# 11-LED.net
KiCad netlist of a schematic drawn in Altium Designer
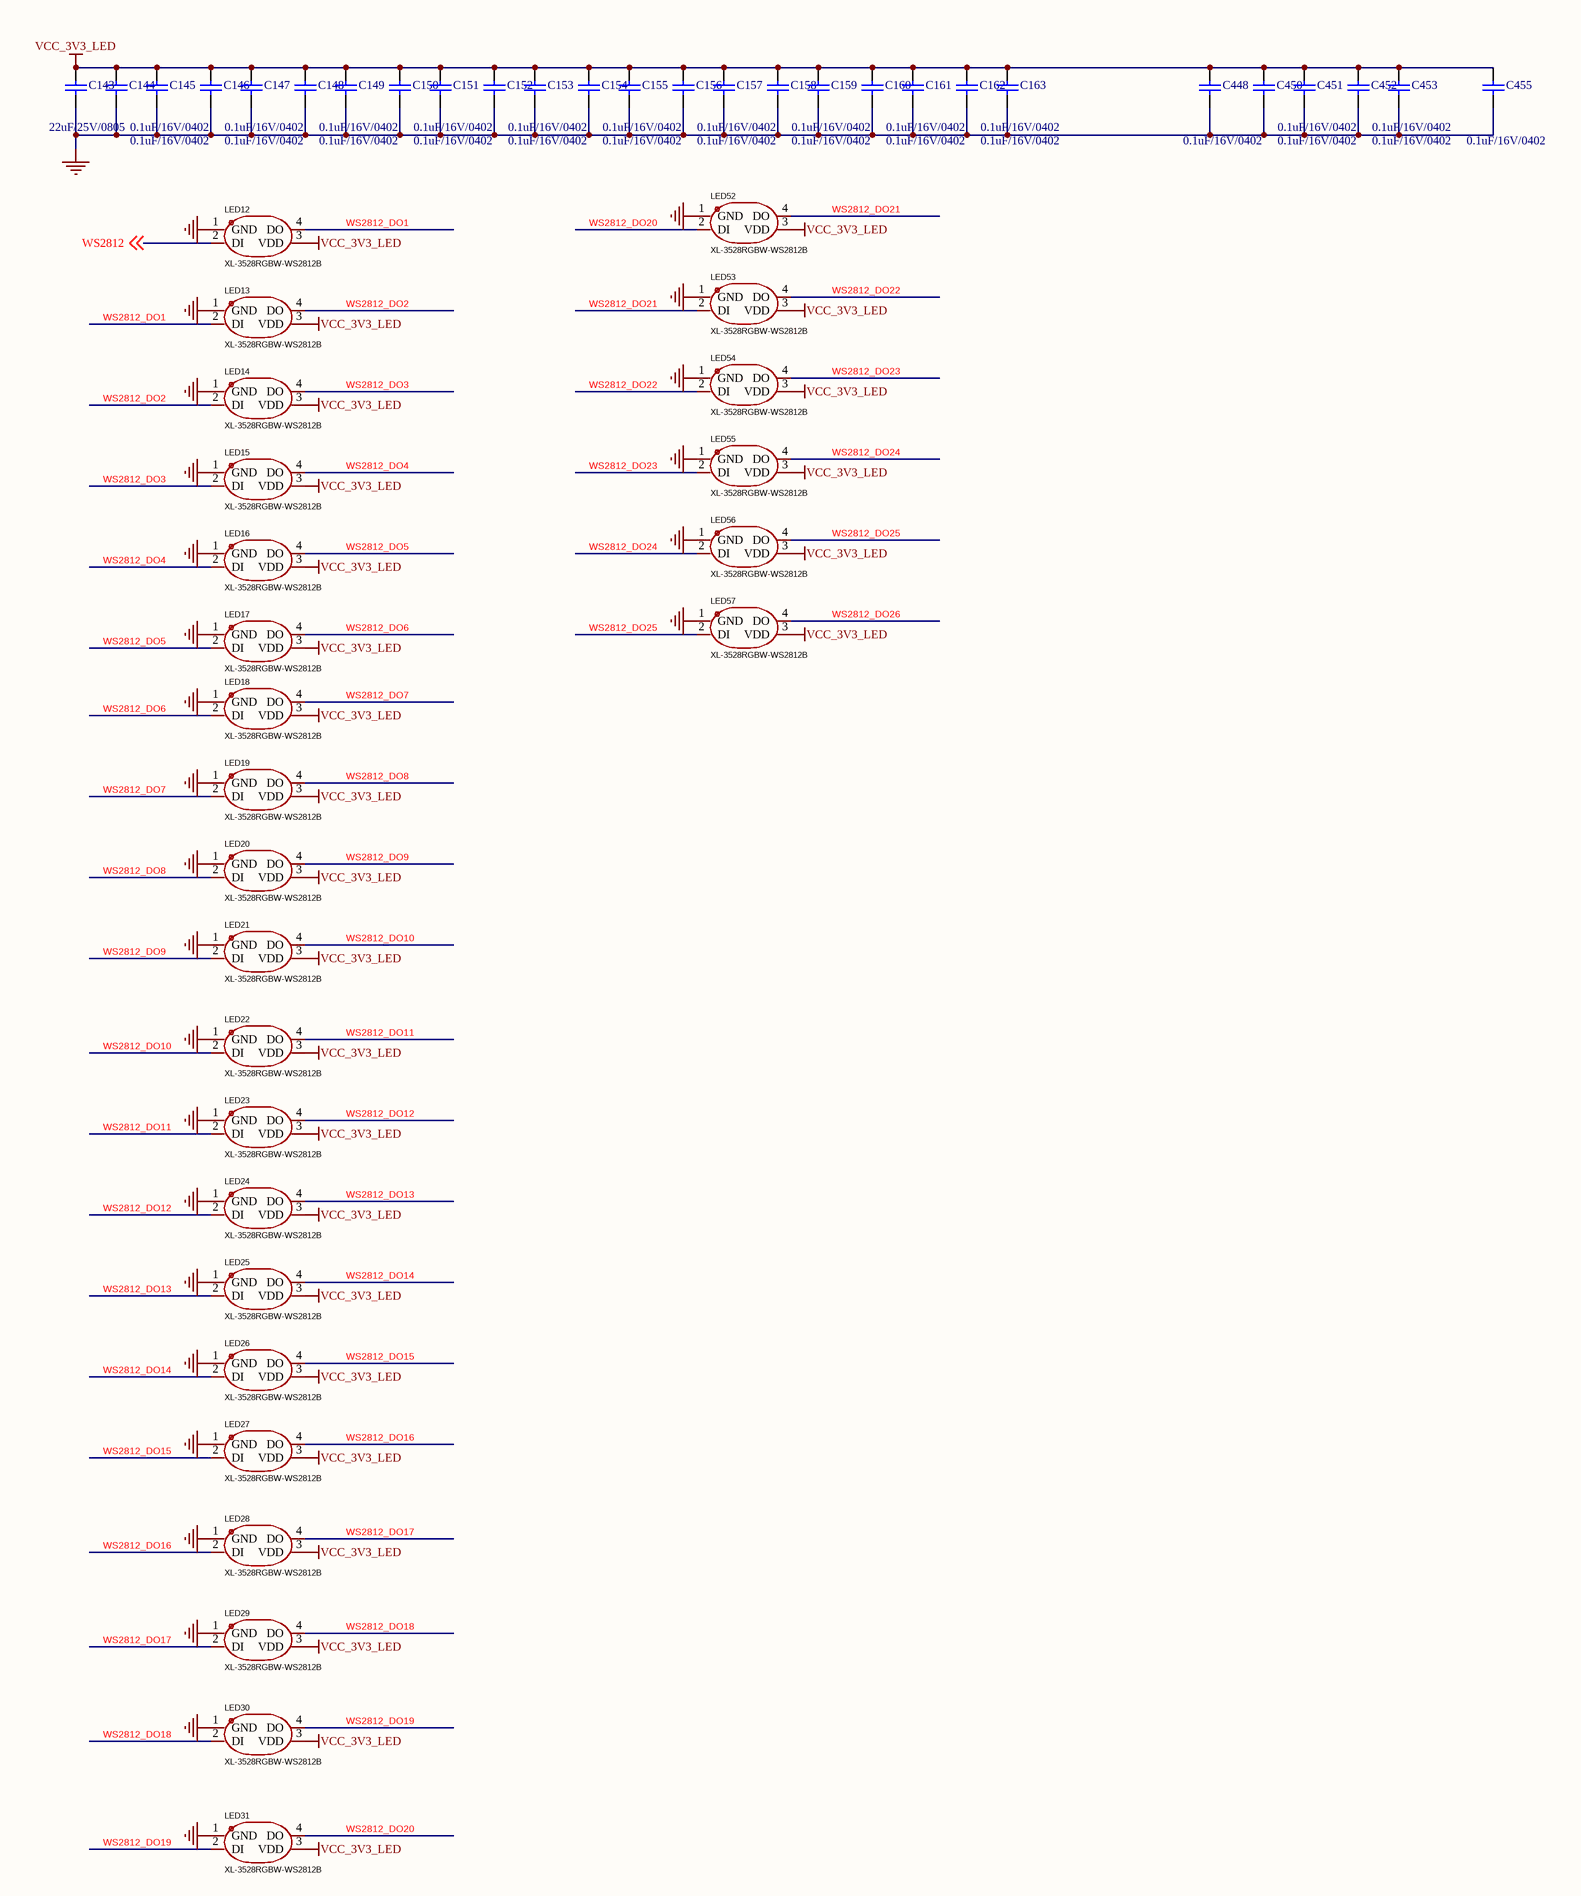
[diagram p0: 11-LED.schdoc]

(export (version "E")
  (design (tool "Eeschema 10.0.6"))
  (components
    (comp (ref "C143")
      (value "22uF/25V/0805")
      (description "Capacitor")
      (fields (field (name "PUBLISHER") "Altium Limited"))
      (libsource (lib "LIBS") (part "CAP"))
    )
    (comp (ref "C144")
      (value "0.1uF/16V/0402")
      (description "Capacitor")
      (fields (field (name "PUBLISHER") "Altium Limited"))
      (libsource (lib "LIBS") (part "CAP"))
    )
    (comp (ref "C145")
      (value "0.1uF/16V/0402")
      (description "Capacitor")
      (fields (field (name "PUBLISHER") "Altium Limited"))
      (libsource (lib "LIBS") (part "CAP"))
    )
    (comp (ref "C146")
      (value "0.1uF/16V/0402")
      (description "Capacitor")
      (fields (field (name "PUBLISHER") "Altium Limited"))
      (libsource (lib "LIBS") (part "CAP"))
    )
    (comp (ref "C147")
      (value "0.1uF/16V/0402")
      (description "Capacitor")
      (fields (field (name "PUBLISHER") "Altium Limited"))
      (libsource (lib "LIBS") (part "CAP"))
    )
    (comp (ref "C148")
      (value "0.1uF/16V/0402")
      (description "Capacitor")
      (fields (field (name "PUBLISHER") "Altium Limited"))
      (libsource (lib "LIBS") (part "CAP"))
    )
    (comp (ref "C149")
      (value "0.1uF/16V/0402")
      (description "Capacitor")
      (fields (field (name "PUBLISHER") "Altium Limited"))
      (libsource (lib "LIBS") (part "CAP"))
    )
    (comp (ref "C150")
      (value "0.1uF/16V/0402")
      (description "Capacitor")
      (fields (field (name "PUBLISHER") "Altium Limited"))
      (libsource (lib "LIBS") (part "CAP"))
    )
    (comp (ref "C151")
      (value "0.1uF/16V/0402")
      (description "Capacitor")
      (fields (field (name "PUBLISHER") "Altium Limited"))
      (libsource (lib "LIBS") (part "CAP"))
    )
    (comp (ref "C152")
      (value "0.1uF/16V/0402")
      (description "Capacitor")
      (fields (field (name "PUBLISHER") "Altium Limited"))
      (libsource (lib "LIBS") (part "CAP"))
    )
    (comp (ref "C153")
      (value "0.1uF/16V/0402")
      (description "Capacitor")
      (fields (field (name "PUBLISHER") "Altium Limited"))
      (libsource (lib "LIBS") (part "CAP"))
    )
    (comp (ref "C154")
      (value "0.1uF/16V/0402")
      (description "Capacitor")
      (fields (field (name "PUBLISHER") "Altium Limited"))
      (libsource (lib "LIBS") (part "CAP"))
    )
    (comp (ref "C155")
      (value "0.1uF/16V/0402")
      (description "Capacitor")
      (fields (field (name "PUBLISHER") "Altium Limited"))
      (libsource (lib "LIBS") (part "CAP"))
    )
    (comp (ref "C156")
      (value "0.1uF/16V/0402")
      (description "Capacitor")
      (fields (field (name "PUBLISHER") "Altium Limited"))
      (libsource (lib "LIBS") (part "CAP"))
    )
    (comp (ref "C157")
      (value "0.1uF/16V/0402")
      (description "Capacitor")
      (fields (field (name "PUBLISHER") "Altium Limited"))
      (libsource (lib "LIBS") (part "CAP"))
    )
    (comp (ref "C158")
      (value "0.1uF/16V/0402")
      (description "Capacitor")
      (fields (field (name "PUBLISHER") "Altium Limited"))
      (libsource (lib "LIBS") (part "CAP"))
    )
    (comp (ref "C159")
      (value "0.1uF/16V/0402")
      (description "Capacitor")
      (fields (field (name "PUBLISHER") "Altium Limited"))
      (libsource (lib "LIBS") (part "CAP"))
    )
    (comp (ref "C160")
      (value "0.1uF/16V/0402")
      (description "Capacitor")
      (fields (field (name "PUBLISHER") "Altium Limited"))
      (libsource (lib "LIBS") (part "CAP"))
    )
    (comp (ref "C161")
      (value "0.1uF/16V/0402")
      (description "Capacitor")
      (fields (field (name "PUBLISHER") "Altium Limited"))
      (libsource (lib "LIBS") (part "CAP"))
    )
    (comp (ref "C162")
      (value "0.1uF/16V/0402")
      (description "Capacitor")
      (fields (field (name "PUBLISHER") "Altium Limited"))
      (libsource (lib "LIBS") (part "CAP"))
    )
    (comp (ref "C163")
      (value "0.1uF/16V/0402")
      (description "Capacitor")
      (fields (field (name "PUBLISHER") "Altium Limited"))
      (libsource (lib "LIBS") (part "CAP"))
    )
    (comp (ref "C448")
      (value "0.1uF/16V/0402")
      (description "Capacitor")
      (fields (field (name "PUBLISHER") "Altium Limited"))
      (libsource (lib "LIBS") (part "CAP"))
    )
    (comp (ref "C450")
      (value "0.1uF/16V/0402")
      (description "Capacitor")
      (fields (field (name "PUBLISHER") "Altium Limited"))
      (libsource (lib "LIBS") (part "CAP"))
    )
    (comp (ref "C451")
      (value "0.1uF/16V/0402")
      (description "Capacitor")
      (fields (field (name "PUBLISHER") "Altium Limited"))
      (libsource (lib "LIBS") (part "CAP"))
    )
    (comp (ref "C452")
      (value "0.1uF/16V/0402")
      (description "Capacitor")
      (fields (field (name "PUBLISHER") "Altium Limited"))
      (libsource (lib "LIBS") (part "CAP"))
    )
    (comp (ref "C453")
      (value "0.1uF/16V/0402")
      (description "Capacitor")
      (fields (field (name "PUBLISHER") "Altium Limited"))
      (libsource (lib "LIBS") (part "CAP"))
    )
    (comp (ref "C455")
      (value "0.1uF/16V/0402")
      (description "Capacitor")
      (fields (field (name "PUBLISHER") "Altium Limited"))
      (libsource (lib "LIBS") (part "CAP"))
    )
    (comp (ref "LED12")
      (value "XL-3528RGBW-WS2812B")
      (footprint "LED-SMD_4P-L3.5-W2.8-BR-1")
      (fields (field (name "MANUFACTURER") "XINGLIGHT(成兴光)"))
      (libsource (lib "altium-import") (part "root_0_XL-3528RGBW-WS2812B_"))
    )
    (comp (ref "LED13")
      (value "XL-3528RGBW-WS2812B")
      (footprint "LED-SMD_4P-L3.5-W2.8-BR-1")
      (fields (field (name "MANUFACTURER") "XINGLIGHT(成兴光)"))
      (libsource (lib "altium-import") (part "root_0_XL-3528RGBW-WS2812B_"))
    )
    (comp (ref "LED14")
      (value "XL-3528RGBW-WS2812B")
      (footprint "LED-SMD_4P-L3.5-W2.8-BR-1")
      (fields (field (name "MANUFACTURER") "XINGLIGHT(成兴光)"))
      (libsource (lib "altium-import") (part "root_0_XL-3528RGBW-WS2812B_"))
    )
    (comp (ref "LED15")
      (value "XL-3528RGBW-WS2812B")
      (footprint "LED-SMD_4P-L3.5-W2.8-BR-1")
      (fields (field (name "MANUFACTURER") "XINGLIGHT(成兴光)"))
      (libsource (lib "altium-import") (part "root_0_XL-3528RGBW-WS2812B_"))
    )
    (comp (ref "LED16")
      (value "XL-3528RGBW-WS2812B")
      (footprint "LED-SMD_4P-L3.5-W2.8-BR-1")
      (fields (field (name "MANUFACTURER") "XINGLIGHT(成兴光)"))
      (libsource (lib "altium-import") (part "root_0_XL-3528RGBW-WS2812B_"))
    )
    (comp (ref "LED17")
      (value "XL-3528RGBW-WS2812B")
      (footprint "LED-SMD_4P-L3.5-W2.8-BR-1")
      (fields (field (name "MANUFACTURER") "XINGLIGHT(成兴光)"))
      (libsource (lib "altium-import") (part "root_0_XL-3528RGBW-WS2812B_"))
    )
    (comp (ref "LED18")
      (value "XL-3528RGBW-WS2812B")
      (footprint "LED-SMD_4P-L3.5-W2.8-BR-1")
      (fields (field (name "MANUFACTURER") "XINGLIGHT(成兴光)"))
      (libsource (lib "altium-import") (part "root_0_XL-3528RGBW-WS2812B_"))
    )
    (comp (ref "LED19")
      (value "XL-3528RGBW-WS2812B")
      (footprint "LED-SMD_4P-L3.5-W2.8-BR-1")
      (fields (field (name "MANUFACTURER") "XINGLIGHT(成兴光)"))
      (libsource (lib "altium-import") (part "root_0_XL-3528RGBW-WS2812B_"))
    )
    (comp (ref "LED20")
      (value "XL-3528RGBW-WS2812B")
      (footprint "LED-SMD_4P-L3.5-W2.8-BR-1")
      (fields (field (name "MANUFACTURER") "XINGLIGHT(成兴光)"))
      (libsource (lib "altium-import") (part "root_0_XL-3528RGBW-WS2812B_"))
    )
    (comp (ref "LED21")
      (value "XL-3528RGBW-WS2812B")
      (footprint "LED-SMD_4P-L3.5-W2.8-BR-1")
      (fields (field (name "MANUFACTURER") "XINGLIGHT(成兴光)"))
      (libsource (lib "altium-import") (part "root_0_XL-3528RGBW-WS2812B_"))
    )
    (comp (ref "LED22")
      (value "XL-3528RGBW-WS2812B")
      (footprint "LED-SMD_4P-L3.5-W2.8-BR-1")
      (fields (field (name "MANUFACTURER") "XINGLIGHT(成兴光)"))
      (libsource (lib "altium-import") (part "root_0_XL-3528RGBW-WS2812B_"))
    )
    (comp (ref "LED23")
      (value "XL-3528RGBW-WS2812B")
      (footprint "LED-SMD_4P-L3.5-W2.8-BR-1")
      (fields (field (name "MANUFACTURER") "XINGLIGHT(成兴光)"))
      (libsource (lib "altium-import") (part "root_0_XL-3528RGBW-WS2812B_"))
    )
    (comp (ref "LED24")
      (value "XL-3528RGBW-WS2812B")
      (footprint "LED-SMD_4P-L3.5-W2.8-BR-1")
      (fields (field (name "MANUFACTURER") "XINGLIGHT(成兴光)"))
      (libsource (lib "altium-import") (part "root_0_XL-3528RGBW-WS2812B_"))
    )
    (comp (ref "LED25")
      (value "XL-3528RGBW-WS2812B")
      (footprint "LED-SMD_4P-L3.5-W2.8-BR-1")
      (fields (field (name "MANUFACTURER") "XINGLIGHT(成兴光)"))
      (libsource (lib "altium-import") (part "root_0_XL-3528RGBW-WS2812B_"))
    )
    (comp (ref "LED26")
      (value "XL-3528RGBW-WS2812B")
      (footprint "LED-SMD_4P-L3.5-W2.8-BR-1")
      (fields (field (name "MANUFACTURER") "XINGLIGHT(成兴光)"))
      (libsource (lib "altium-import") (part "root_0_XL-3528RGBW-WS2812B_"))
    )
    (comp (ref "LED27")
      (value "XL-3528RGBW-WS2812B")
      (footprint "LED-SMD_4P-L3.5-W2.8-BR-1")
      (fields (field (name "MANUFACTURER") "XINGLIGHT(成兴光)"))
      (libsource (lib "altium-import") (part "root_0_XL-3528RGBW-WS2812B_"))
    )
    (comp (ref "LED28")
      (value "XL-3528RGBW-WS2812B")
      (footprint "LED-SMD_4P-L3.5-W2.8-BR-1")
      (fields (field (name "MANUFACTURER") "XINGLIGHT(成兴光)"))
      (libsource (lib "altium-import") (part "root_0_XL-3528RGBW-WS2812B_"))
    )
    (comp (ref "LED29")
      (value "XL-3528RGBW-WS2812B")
      (footprint "LED-SMD_4P-L3.5-W2.8-BR-1")
      (fields (field (name "MANUFACTURER") "XINGLIGHT(成兴光)"))
      (libsource (lib "altium-import") (part "root_0_XL-3528RGBW-WS2812B_"))
    )
    (comp (ref "LED30")
      (value "XL-3528RGBW-WS2812B")
      (footprint "LED-SMD_4P-L3.5-W2.8-BR-1")
      (fields (field (name "MANUFACTURER") "XINGLIGHT(成兴光)"))
      (libsource (lib "altium-import") (part "root_0_XL-3528RGBW-WS2812B_"))
    )
    (comp (ref "LED31")
      (value "XL-3528RGBW-WS2812B")
      (footprint "LED-SMD_4P-L3.5-W2.8-BR-1")
      (fields (field (name "MANUFACTURER") "XINGLIGHT(成兴光)"))
      (libsource (lib "altium-import") (part "root_0_XL-3528RGBW-WS2812B_"))
    )
    (comp (ref "LED52")
      (value "XL-3528RGBW-WS2812B")
      (footprint "LED-SMD_4P-L3.5-W2.8-BR-1")
      (fields (field (name "MANUFACTURER") "XINGLIGHT(成兴光)"))
      (libsource (lib "altium-import") (part "root_0_XL-3528RGBW-WS2812B_"))
    )
    (comp (ref "LED53")
      (value "XL-3528RGBW-WS2812B")
      (footprint "LED-SMD_4P-L3.5-W2.8-BR-1")
      (fields (field (name "MANUFACTURER") "XINGLIGHT(成兴光)"))
      (libsource (lib "altium-import") (part "root_0_XL-3528RGBW-WS2812B_"))
    )
    (comp (ref "LED54")
      (value "XL-3528RGBW-WS2812B")
      (footprint "LED-SMD_4P-L3.5-W2.8-BR-1")
      (fields (field (name "MANUFACTURER") "XINGLIGHT(成兴光)"))
      (libsource (lib "altium-import") (part "root_0_XL-3528RGBW-WS2812B_"))
    )
    (comp (ref "LED55")
      (value "XL-3528RGBW-WS2812B")
      (footprint "LED-SMD_4P-L3.5-W2.8-BR-1")
      (fields (field (name "MANUFACTURER") "XINGLIGHT(成兴光)"))
      (libsource (lib "altium-import") (part "root_0_XL-3528RGBW-WS2812B_"))
    )
    (comp (ref "LED56")
      (value "XL-3528RGBW-WS2812B")
      (footprint "LED-SMD_4P-L3.5-W2.8-BR-1")
      (fields (field (name "MANUFACTURER") "XINGLIGHT(成兴光)"))
      (libsource (lib "altium-import") (part "root_0_XL-3528RGBW-WS2812B_"))
    )
    (comp (ref "LED57")
      (value "XL-3528RGBW-WS2812B")
      (footprint "LED-SMD_4P-L3.5-W2.8-BR-1")
      (fields (field (name "MANUFACTURER") "XINGLIGHT(成兴光)"))
      (libsource (lib "altium-import") (part "root_0_XL-3528RGBW-WS2812B_"))
    )
  )
  (nets
    (net (code "1") (name "/WS2812_DO1") (class "Default")
      (node (ref "LED12") (pin "4") (pinfunction "DO_4") (pintype "passive"))
      (node (ref "LED13") (pin "2") (pinfunction "DI_2") (pintype "passive"))
    )
    (net (code "2") (name "/WS2812_DO2") (class "Default")
      (node (ref "LED13") (pin "4") (pinfunction "DO_4") (pintype "passive"))
      (node (ref "LED14") (pin "2") (pinfunction "DI_2") (pintype "passive"))
    )
    (net (code "3") (name "/WS2812_DO3") (class "Default")
      (node (ref "LED14") (pin "4") (pinfunction "DO_4") (pintype "passive"))
      (node (ref "LED15") (pin "2") (pinfunction "DI_2") (pintype "passive"))
    )
    (net (code "4") (name "/WS2812_DO4") (class "Default")
      (node (ref "LED15") (pin "4") (pinfunction "DO_4") (pintype "passive"))
      (node (ref "LED16") (pin "2") (pinfunction "DI_2") (pintype "passive"))
    )
    (net (code "5") (name "/WS2812_DO5") (class "Default")
      (node (ref "LED16") (pin "4") (pinfunction "DO_4") (pintype "passive"))
      (node (ref "LED17") (pin "2") (pinfunction "DI_2") (pintype "passive"))
    )
    (net (code "6") (name "/WS2812_DO6") (class "Default")
      (node (ref "LED17") (pin "4") (pinfunction "DO_4") (pintype "passive"))
      (node (ref "LED18") (pin "2") (pinfunction "DI_2") (pintype "passive"))
    )
    (net (code "7") (name "/WS2812_DO7") (class "Default")
      (node (ref "LED18") (pin "4") (pinfunction "DO_4") (pintype "passive"))
      (node (ref "LED19") (pin "2") (pinfunction "DI_2") (pintype "passive"))
    )
    (net (code "8") (name "/WS2812_DO8") (class "Default")
      (node (ref "LED19") (pin "4") (pinfunction "DO_4") (pintype "passive"))
      (node (ref "LED20") (pin "2") (pinfunction "DI_2") (pintype "passive"))
    )
    (net (code "9") (name "/WS2812_DO9") (class "Default")
      (node (ref "LED20") (pin "4") (pinfunction "DO_4") (pintype "passive"))
      (node (ref "LED21") (pin "2") (pinfunction "DI_2") (pintype "passive"))
    )
    (net (code "10") (name "/WS2812_DO10") (class "Default")
      (node (ref "LED21") (pin "4") (pinfunction "DO_4") (pintype "passive"))
      (node (ref "LED22") (pin "2") (pinfunction "DI_2") (pintype "passive"))
    )
    (net (code "11") (name "/WS2812_DO11") (class "Default")
      (node (ref "LED22") (pin "4") (pinfunction "DO_4") (pintype "passive"))
      (node (ref "LED23") (pin "2") (pinfunction "DI_2") (pintype "passive"))
    )
    (net (code "12") (name "/WS2812_DO12") (class "Default")
      (node (ref "LED23") (pin "4") (pinfunction "DO_4") (pintype "passive"))
      (node (ref "LED24") (pin "2") (pinfunction "DI_2") (pintype "passive"))
    )
    (net (code "13") (name "/WS2812_DO13") (class "Default")
      (node (ref "LED24") (pin "4") (pinfunction "DO_4") (pintype "passive"))
      (node (ref "LED25") (pin "2") (pinfunction "DI_2") (pintype "passive"))
    )
    (net (code "14") (name "/WS2812_DO14") (class "Default")
      (node (ref "LED25") (pin "4") (pinfunction "DO_4") (pintype "passive"))
      (node (ref "LED26") (pin "2") (pinfunction "DI_2") (pintype "passive"))
    )
    (net (code "15") (name "/WS2812_DO15") (class "Default")
      (node (ref "LED26") (pin "4") (pinfunction "DO_4") (pintype "passive"))
      (node (ref "LED27") (pin "2") (pinfunction "DI_2") (pintype "passive"))
    )
    (net (code "16") (name "/WS2812_DO16") (class "Default")
      (node (ref "LED27") (pin "4") (pinfunction "DO_4") (pintype "passive"))
      (node (ref "LED28") (pin "2") (pinfunction "DI_2") (pintype "passive"))
    )
    (net (code "17") (name "/WS2812_DO17") (class "Default")
      (node (ref "LED28") (pin "4") (pinfunction "DO_4") (pintype "passive"))
      (node (ref "LED29") (pin "2") (pinfunction "DI_2") (pintype "passive"))
    )
    (net (code "18") (name "/WS2812_DO18") (class "Default")
      (node (ref "LED29") (pin "4") (pinfunction "DO_4") (pintype "passive"))
      (node (ref "LED30") (pin "2") (pinfunction "DI_2") (pintype "passive"))
    )
    (net (code "19") (name "/WS2812_DO19") (class "Default")
      (node (ref "LED30") (pin "4") (pinfunction "DO_4") (pintype "passive"))
      (node (ref "LED31") (pin "2") (pinfunction "DI_2") (pintype "passive"))
    )
    (net (code "20") (name "/WS2812_DO20") (class "Default")
      (node (ref "LED31") (pin "4") (pinfunction "DO_4") (pintype "passive"))
      (node (ref "LED52") (pin "2") (pinfunction "DI_2") (pintype "passive"))
    )
    (net (code "21") (name "/WS2812_DO21") (class "Default")
      (node (ref "LED52") (pin "4") (pinfunction "DO_4") (pintype "passive"))
      (node (ref "LED53") (pin "2") (pinfunction "DI_2") (pintype "passive"))
    )
    (net (code "22") (name "/WS2812_DO22") (class "Default")
      (node (ref "LED53") (pin "4") (pinfunction "DO_4") (pintype "passive"))
      (node (ref "LED54") (pin "2") (pinfunction "DI_2") (pintype "passive"))
    )
    (net (code "23") (name "/WS2812_DO23") (class "Default")
      (node (ref "LED54") (pin "4") (pinfunction "DO_4") (pintype "passive"))
      (node (ref "LED55") (pin "2") (pinfunction "DI_2") (pintype "passive"))
    )
    (net (code "24") (name "/WS2812_DO24") (class "Default")
      (node (ref "LED55") (pin "4") (pinfunction "DO_4") (pintype "passive"))
      (node (ref "LED56") (pin "2") (pinfunction "DI_2") (pintype "passive"))
    )
    (net (code "25") (name "/WS2812_DO25") (class "Default")
      (node (ref "LED56") (pin "4") (pinfunction "DO_4") (pintype "passive"))
      (node (ref "LED57") (pin "2") (pinfunction "DI_2") (pintype "passive"))
    )
    (net (code "26") (name "/WS2812_DO26") (class "Default")
      (node (ref "LED57") (pin "4") (pinfunction "DO_4") (pintype "passive"))
    )
    (net (code "27") (name "GND") (class "Default")
      (node (ref "C143") (pin "1") (pinfunction "1_1") (pintype "passive"))
      (node (ref "C144") (pin "1") (pinfunction "1_1") (pintype "passive"))
      (node (ref "C145") (pin "1") (pinfunction "1_1") (pintype "passive"))
      (node (ref "C146") (pin "1") (pinfunction "1_1") (pintype "passive"))
      (node (ref "C147") (pin "1") (pinfunction "1_1") (pintype "passive"))
      (node (ref "C148") (pin "1") (pinfunction "1_1") (pintype "passive"))
      (node (ref "C149") (pin "1") (pinfunction "1_1") (pintype "passive"))
      (node (ref "C150") (pin "1") (pinfunction "1_1") (pintype "passive"))
      (node (ref "C151") (pin "1") (pinfunction "1_1") (pintype "passive"))
      (node (ref "C152") (pin "1") (pinfunction "1_1") (pintype "passive"))
      (node (ref "C153") (pin "1") (pinfunction "1_1") (pintype "passive"))
      (node (ref "C154") (pin "1") (pinfunction "1_1") (pintype "passive"))
      (node (ref "C155") (pin "1") (pinfunction "1_1") (pintype "passive"))
      (node (ref "C156") (pin "1") (pinfunction "1_1") (pintype "passive"))
      (node (ref "C157") (pin "1") (pinfunction "1_1") (pintype "passive"))
      (node (ref "C158") (pin "1") (pinfunction "1_1") (pintype "passive"))
      (node (ref "C159") (pin "1") (pinfunction "1_1") (pintype "passive"))
      (node (ref "C160") (pin "1") (pinfunction "1_1") (pintype "passive"))
      (node (ref "C161") (pin "1") (pinfunction "1_1") (pintype "passive"))
      (node (ref "C162") (pin "1") (pinfunction "1_1") (pintype "passive"))
      (node (ref "C163") (pin "1") (pinfunction "1_1") (pintype "passive"))
      (node (ref "C448") (pin "1") (pinfunction "1_1") (pintype "passive"))
      (node (ref "C450") (pin "1") (pinfunction "1_1") (pintype "passive"))
      (node (ref "C451") (pin "1") (pinfunction "1_1") (pintype "passive"))
      (node (ref "C452") (pin "1") (pinfunction "1_1") (pintype "passive"))
      (node (ref "C453") (pin "1") (pinfunction "1_1") (pintype "passive"))
      (node (ref "C455") (pin "1") (pinfunction "1_1") (pintype "passive"))
      (node (ref "LED12") (pin "1") (pinfunction "GND_1") (pintype "passive"))
      (node (ref "LED13") (pin "1") (pinfunction "GND_1") (pintype "passive"))
      (node (ref "LED14") (pin "1") (pinfunction "GND_1") (pintype "passive"))
      (node (ref "LED15") (pin "1") (pinfunction "GND_1") (pintype "passive"))
      (node (ref "LED16") (pin "1") (pinfunction "GND_1") (pintype "passive"))
      (node (ref "LED17") (pin "1") (pinfunction "GND_1") (pintype "passive"))
      (node (ref "LED18") (pin "1") (pinfunction "GND_1") (pintype "passive"))
      (node (ref "LED19") (pin "1") (pinfunction "GND_1") (pintype "passive"))
      (node (ref "LED20") (pin "1") (pinfunction "GND_1") (pintype "passive"))
      (node (ref "LED21") (pin "1") (pinfunction "GND_1") (pintype "passive"))
      (node (ref "LED22") (pin "1") (pinfunction "GND_1") (pintype "passive"))
      (node (ref "LED23") (pin "1") (pinfunction "GND_1") (pintype "passive"))
      (node (ref "LED24") (pin "1") (pinfunction "GND_1") (pintype "passive"))
      (node (ref "LED25") (pin "1") (pinfunction "GND_1") (pintype "passive"))
      (node (ref "LED26") (pin "1") (pinfunction "GND_1") (pintype "passive"))
      (node (ref "LED27") (pin "1") (pinfunction "GND_1") (pintype "passive"))
      (node (ref "LED28") (pin "1") (pinfunction "GND_1") (pintype "passive"))
      (node (ref "LED29") (pin "1") (pinfunction "GND_1") (pintype "passive"))
      (node (ref "LED30") (pin "1") (pinfunction "GND_1") (pintype "passive"))
      (node (ref "LED31") (pin "1") (pinfunction "GND_1") (pintype "passive"))
      (node (ref "LED52") (pin "1") (pinfunction "GND_1") (pintype "passive"))
      (node (ref "LED53") (pin "1") (pinfunction "GND_1") (pintype "passive"))
      (node (ref "LED54") (pin "1") (pinfunction "GND_1") (pintype "passive"))
      (node (ref "LED55") (pin "1") (pinfunction "GND_1") (pintype "passive"))
      (node (ref "LED56") (pin "1") (pinfunction "GND_1") (pintype "passive"))
      (node (ref "LED57") (pin "1") (pinfunction "GND_1") (pintype "passive"))
    )
    (net (code "28") (name "VCC_3V3_LED") (class "Default")
      (node (ref "C143") (pin "2") (pinfunction "2_2") (pintype "passive"))
      (node (ref "C144") (pin "2") (pinfunction "2_2") (pintype "passive"))
      (node (ref "C145") (pin "2") (pinfunction "2_2") (pintype "passive"))
      (node (ref "C146") (pin "2") (pinfunction "2_2") (pintype "passive"))
      (node (ref "C147") (pin "2") (pinfunction "2_2") (pintype "passive"))
      (node (ref "C148") (pin "2") (pinfunction "2_2") (pintype "passive"))
      (node (ref "C149") (pin "2") (pinfunction "2_2") (pintype "passive"))
      (node (ref "C150") (pin "2") (pinfunction "2_2") (pintype "passive"))
      (node (ref "C151") (pin "2") (pinfunction "2_2") (pintype "passive"))
      (node (ref "C152") (pin "2") (pinfunction "2_2") (pintype "passive"))
      (node (ref "C153") (pin "2") (pinfunction "2_2") (pintype "passive"))
      (node (ref "C154") (pin "2") (pinfunction "2_2") (pintype "passive"))
      (node (ref "C155") (pin "2") (pinfunction "2_2") (pintype "passive"))
      (node (ref "C156") (pin "2") (pinfunction "2_2") (pintype "passive"))
      (node (ref "C157") (pin "2") (pinfunction "2_2") (pintype "passive"))
      (node (ref "C158") (pin "2") (pinfunction "2_2") (pintype "passive"))
      (node (ref "C159") (pin "2") (pinfunction "2_2") (pintype "passive"))
      (node (ref "C160") (pin "2") (pinfunction "2_2") (pintype "passive"))
      (node (ref "C161") (pin "2") (pinfunction "2_2") (pintype "passive"))
      (node (ref "C162") (pin "2") (pinfunction "2_2") (pintype "passive"))
      (node (ref "C163") (pin "2") (pinfunction "2_2") (pintype "passive"))
      (node (ref "C448") (pin "2") (pinfunction "2_2") (pintype "passive"))
      (node (ref "C450") (pin "2") (pinfunction "2_2") (pintype "passive"))
      (node (ref "C451") (pin "2") (pinfunction "2_2") (pintype "passive"))
      (node (ref "C452") (pin "2") (pinfunction "2_2") (pintype "passive"))
      (node (ref "C453") (pin "2") (pinfunction "2_2") (pintype "passive"))
      (node (ref "C455") (pin "2") (pinfunction "2_2") (pintype "passive"))
      (node (ref "LED12") (pin "3") (pinfunction "VDD_3") (pintype "passive"))
      (node (ref "LED13") (pin "3") (pinfunction "VDD_3") (pintype "passive"))
      (node (ref "LED14") (pin "3") (pinfunction "VDD_3") (pintype "passive"))
      (node (ref "LED15") (pin "3") (pinfunction "VDD_3") (pintype "passive"))
      (node (ref "LED16") (pin "3") (pinfunction "VDD_3") (pintype "passive"))
      (node (ref "LED17") (pin "3") (pinfunction "VDD_3") (pintype "passive"))
      (node (ref "LED18") (pin "3") (pinfunction "VDD_3") (pintype "passive"))
      (node (ref "LED19") (pin "3") (pinfunction "VDD_3") (pintype "passive"))
      (node (ref "LED20") (pin "3") (pinfunction "VDD_3") (pintype "passive"))
      (node (ref "LED21") (pin "3") (pinfunction "VDD_3") (pintype "passive"))
      (node (ref "LED22") (pin "3") (pinfunction "VDD_3") (pintype "passive"))
      (node (ref "LED23") (pin "3") (pinfunction "VDD_3") (pintype "passive"))
      (node (ref "LED24") (pin "3") (pinfunction "VDD_3") (pintype "passive"))
      (node (ref "LED25") (pin "3") (pinfunction "VDD_3") (pintype "passive"))
      (node (ref "LED26") (pin "3") (pinfunction "VDD_3") (pintype "passive"))
      (node (ref "LED27") (pin "3") (pinfunction "VDD_3") (pintype "passive"))
      (node (ref "LED28") (pin "3") (pinfunction "VDD_3") (pintype "passive"))
      (node (ref "LED29") (pin "3") (pinfunction "VDD_3") (pintype "passive"))
      (node (ref "LED30") (pin "3") (pinfunction "VDD_3") (pintype "passive"))
      (node (ref "LED31") (pin "3") (pinfunction "VDD_3") (pintype "passive"))
      (node (ref "LED52") (pin "3") (pinfunction "VDD_3") (pintype "passive"))
      (node (ref "LED53") (pin "3") (pinfunction "VDD_3") (pintype "passive"))
      (node (ref "LED54") (pin "3") (pinfunction "VDD_3") (pintype "passive"))
      (node (ref "LED55") (pin "3") (pinfunction "VDD_3") (pintype "passive"))
      (node (ref "LED56") (pin "3") (pinfunction "VDD_3") (pintype "passive"))
      (node (ref "LED57") (pin "3") (pinfunction "VDD_3") (pintype "passive"))
    )
    (net (code "29") (name "WS2812") (class "Default")
      (node (ref "LED12") (pin "2") (pinfunction "DI_2") (pintype "passive"))
    )
  )
)
